# PCB_Telemetria_2020.net
KiCad netlist of a schematic drawn in EAGLE
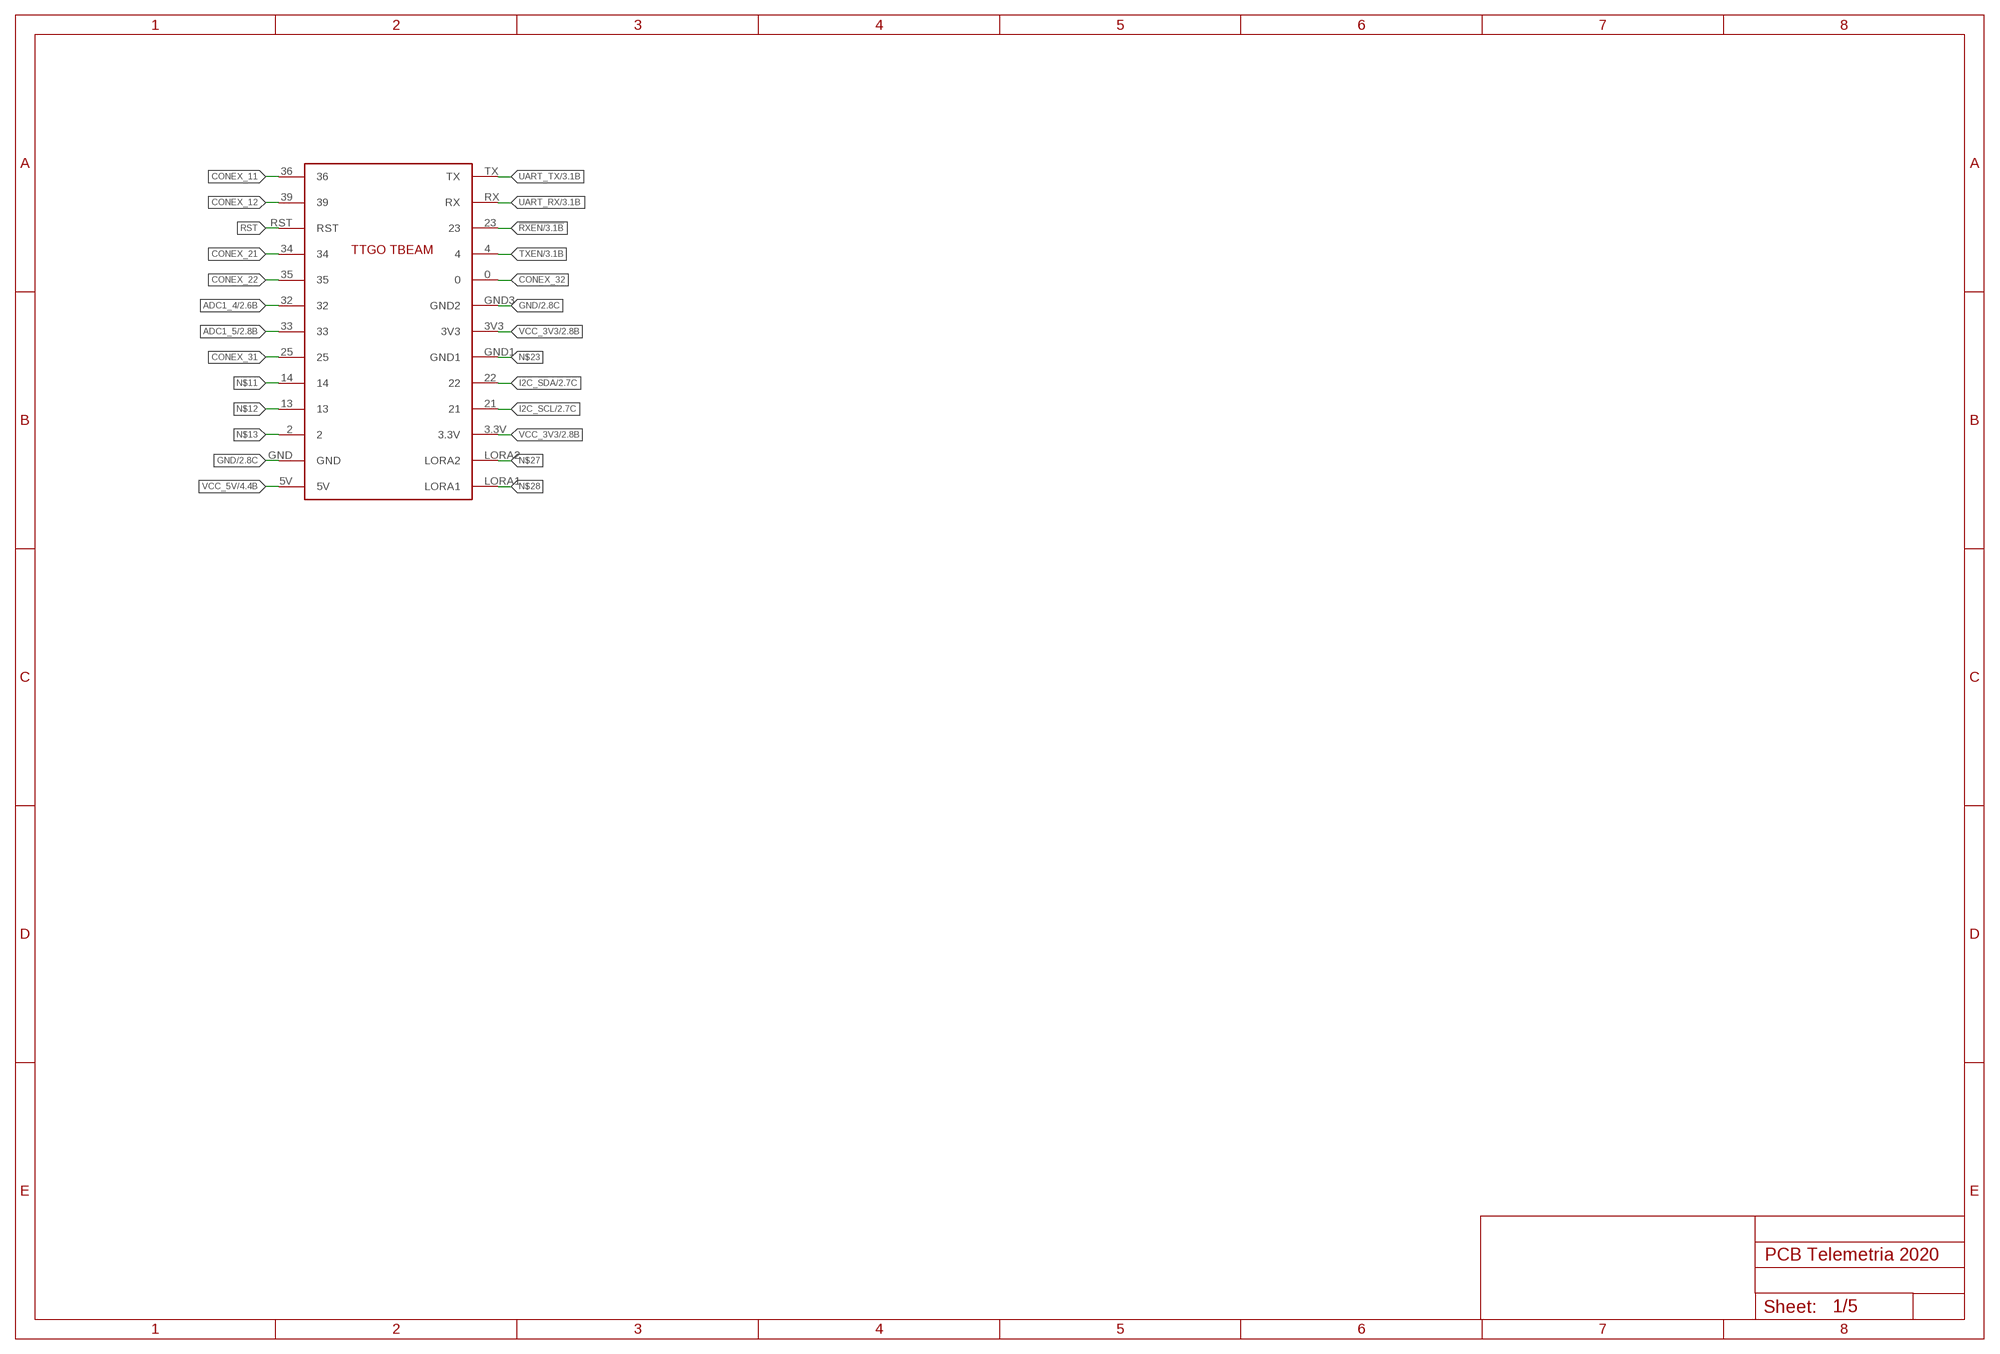
[diagram p0: schematic, sheet 1]
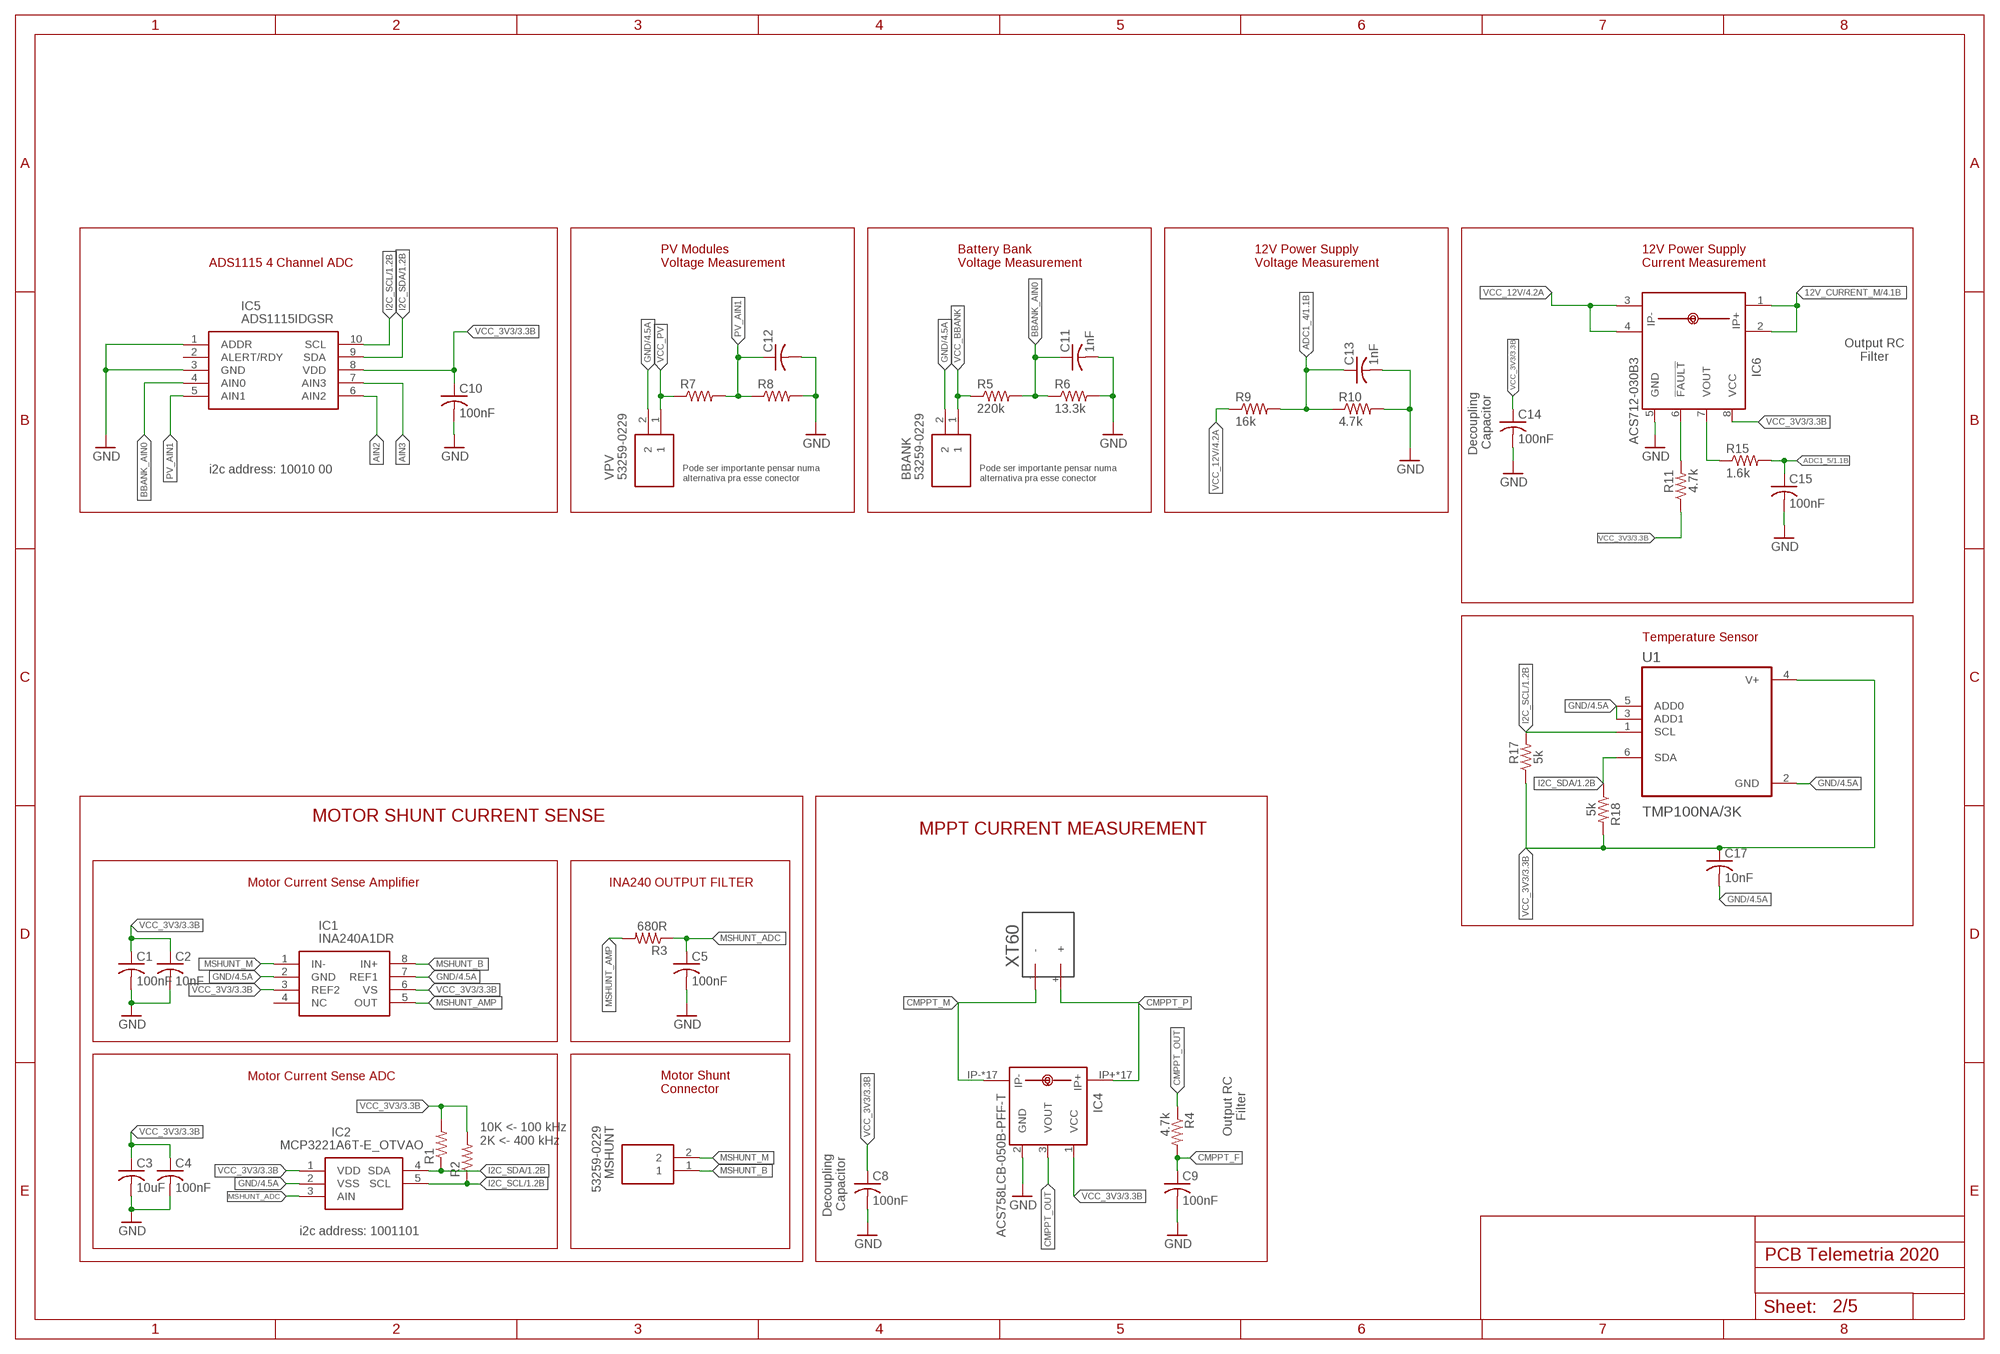
[diagram p1: schematic, sheet 2]
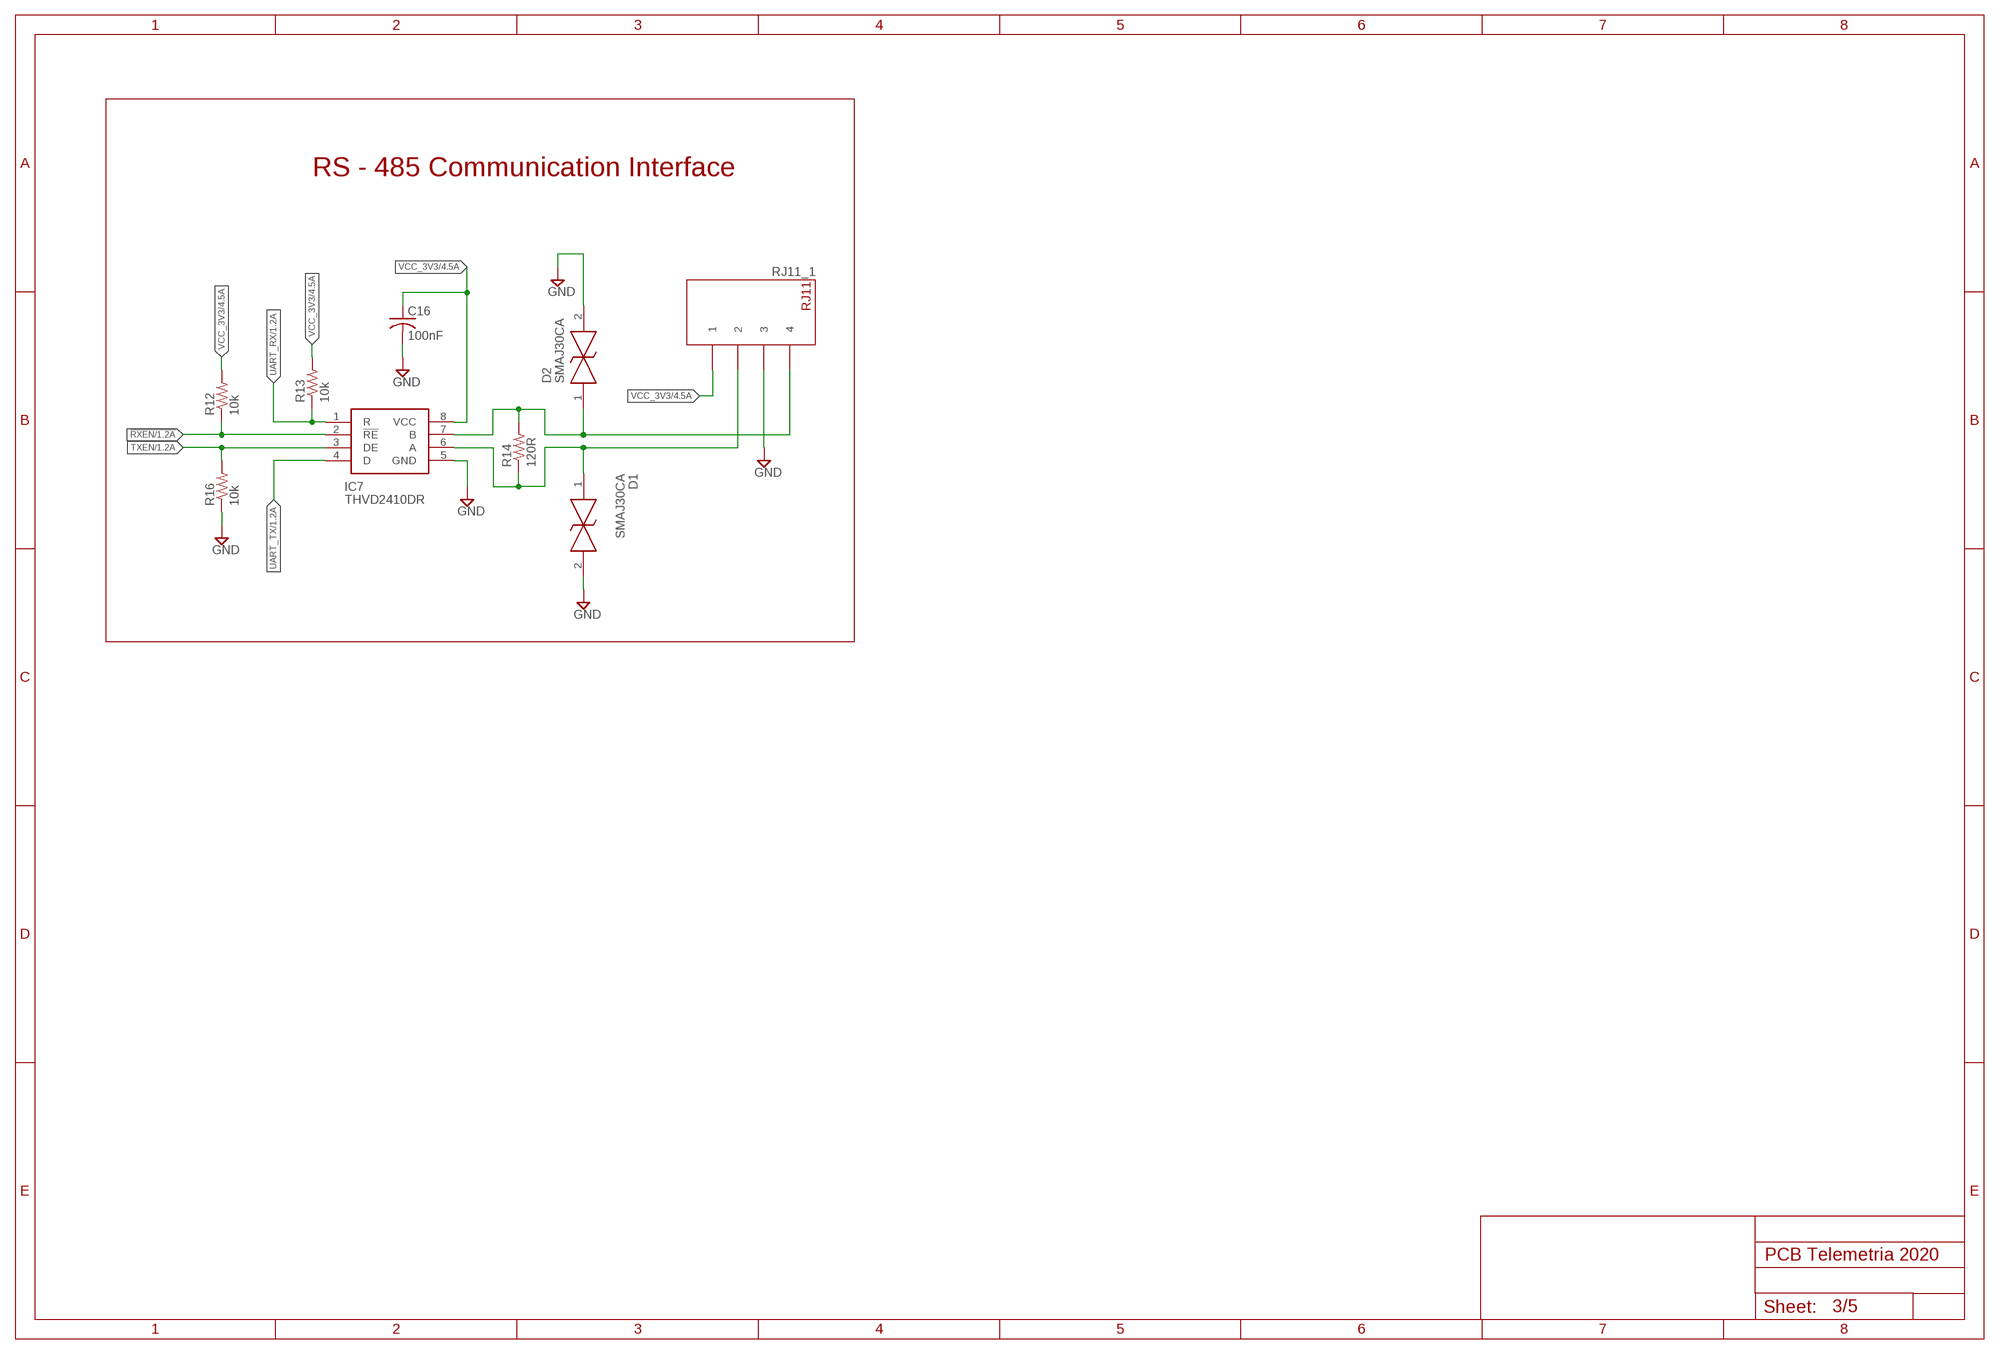
[diagram p2: schematic, sheet 3]
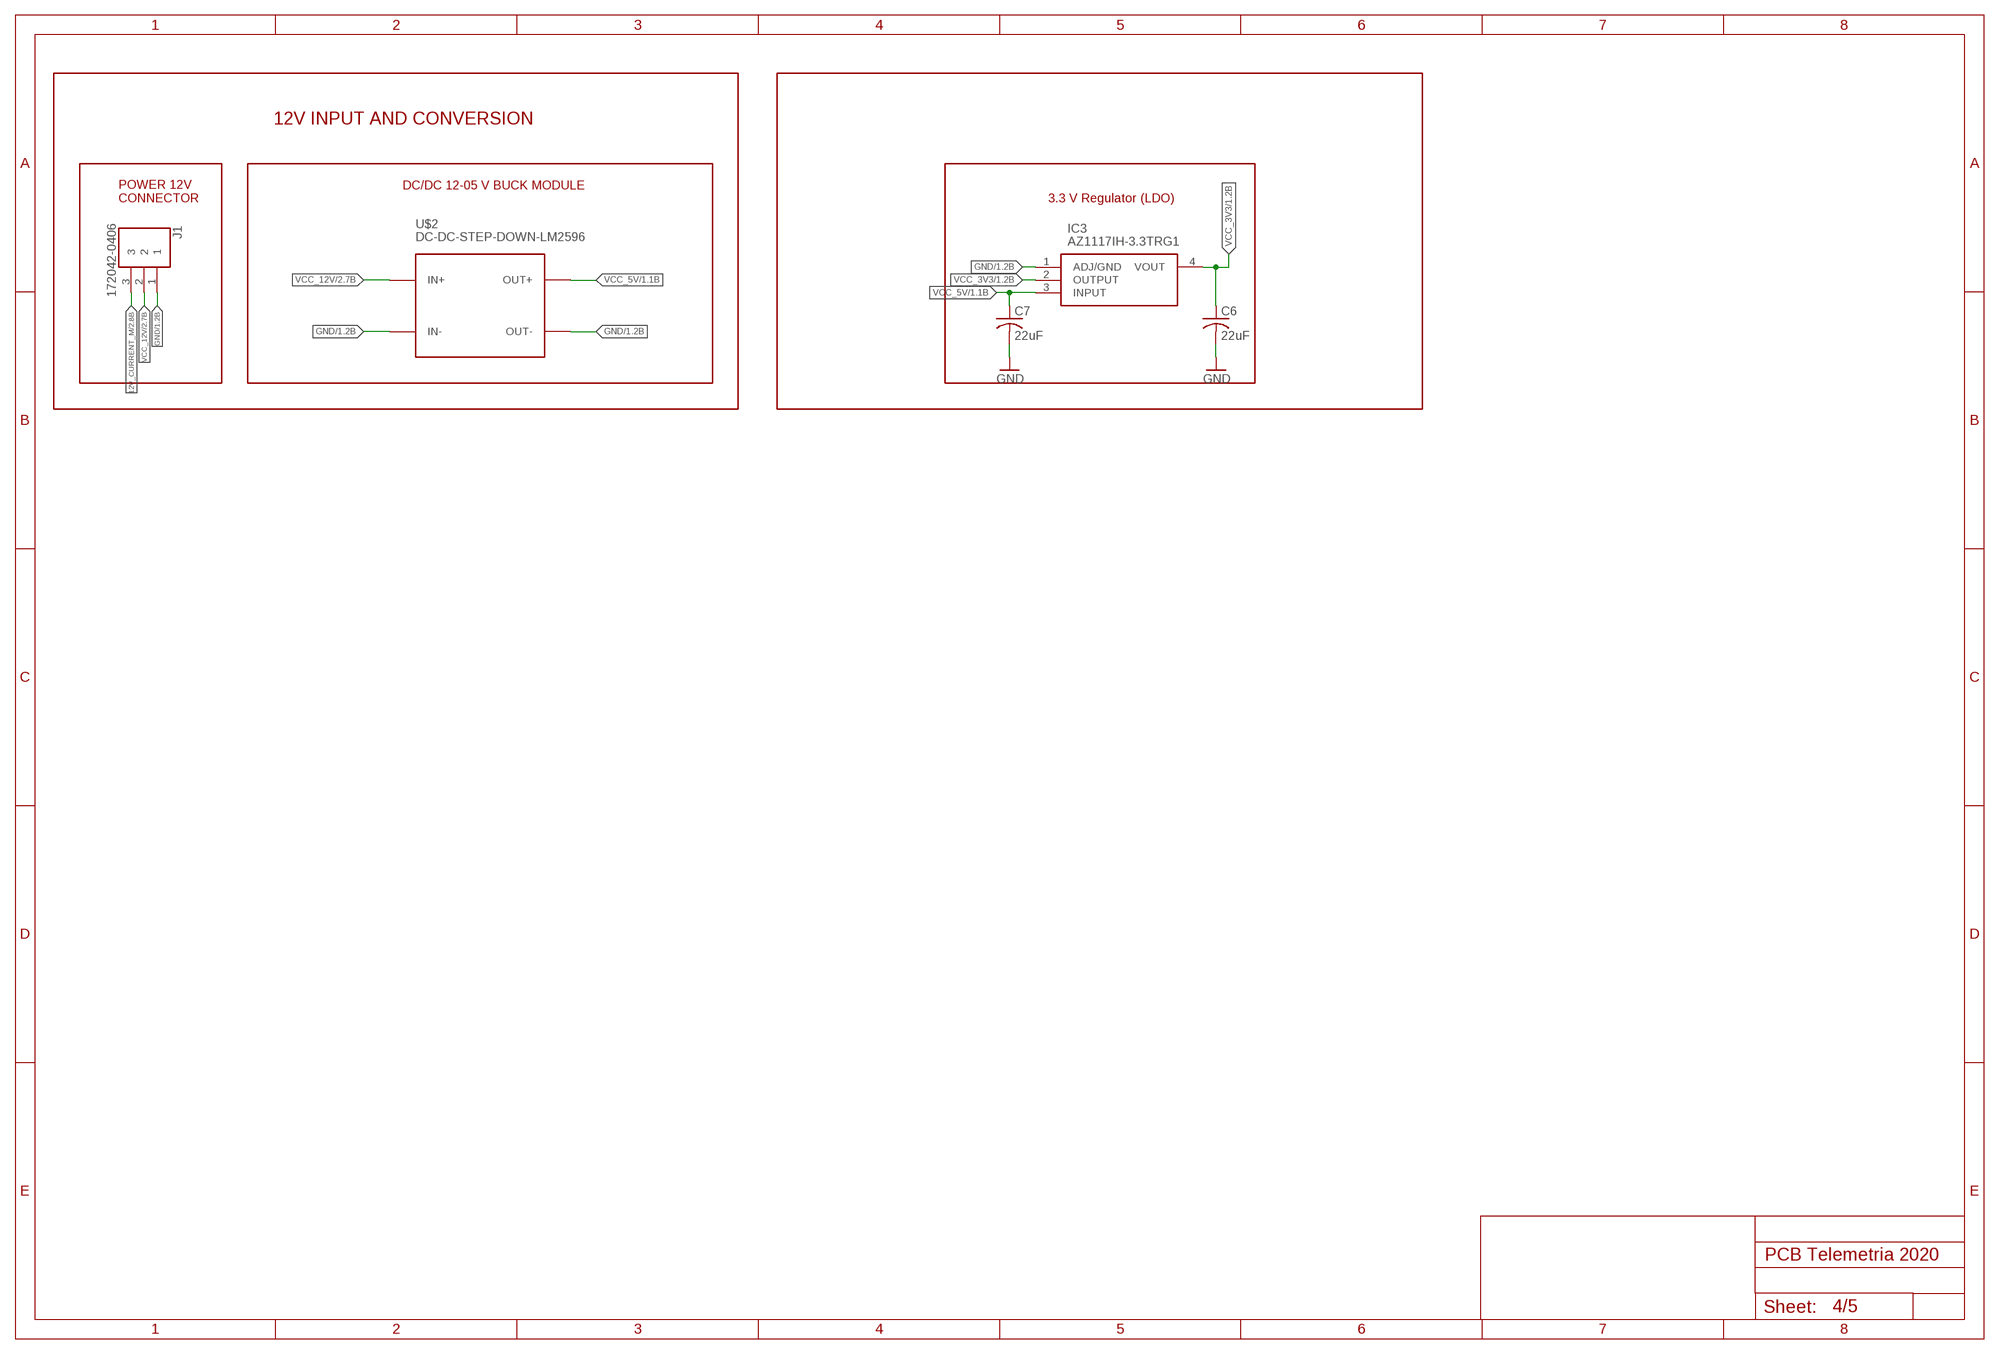
[diagram p3: schematic, sheet 4]
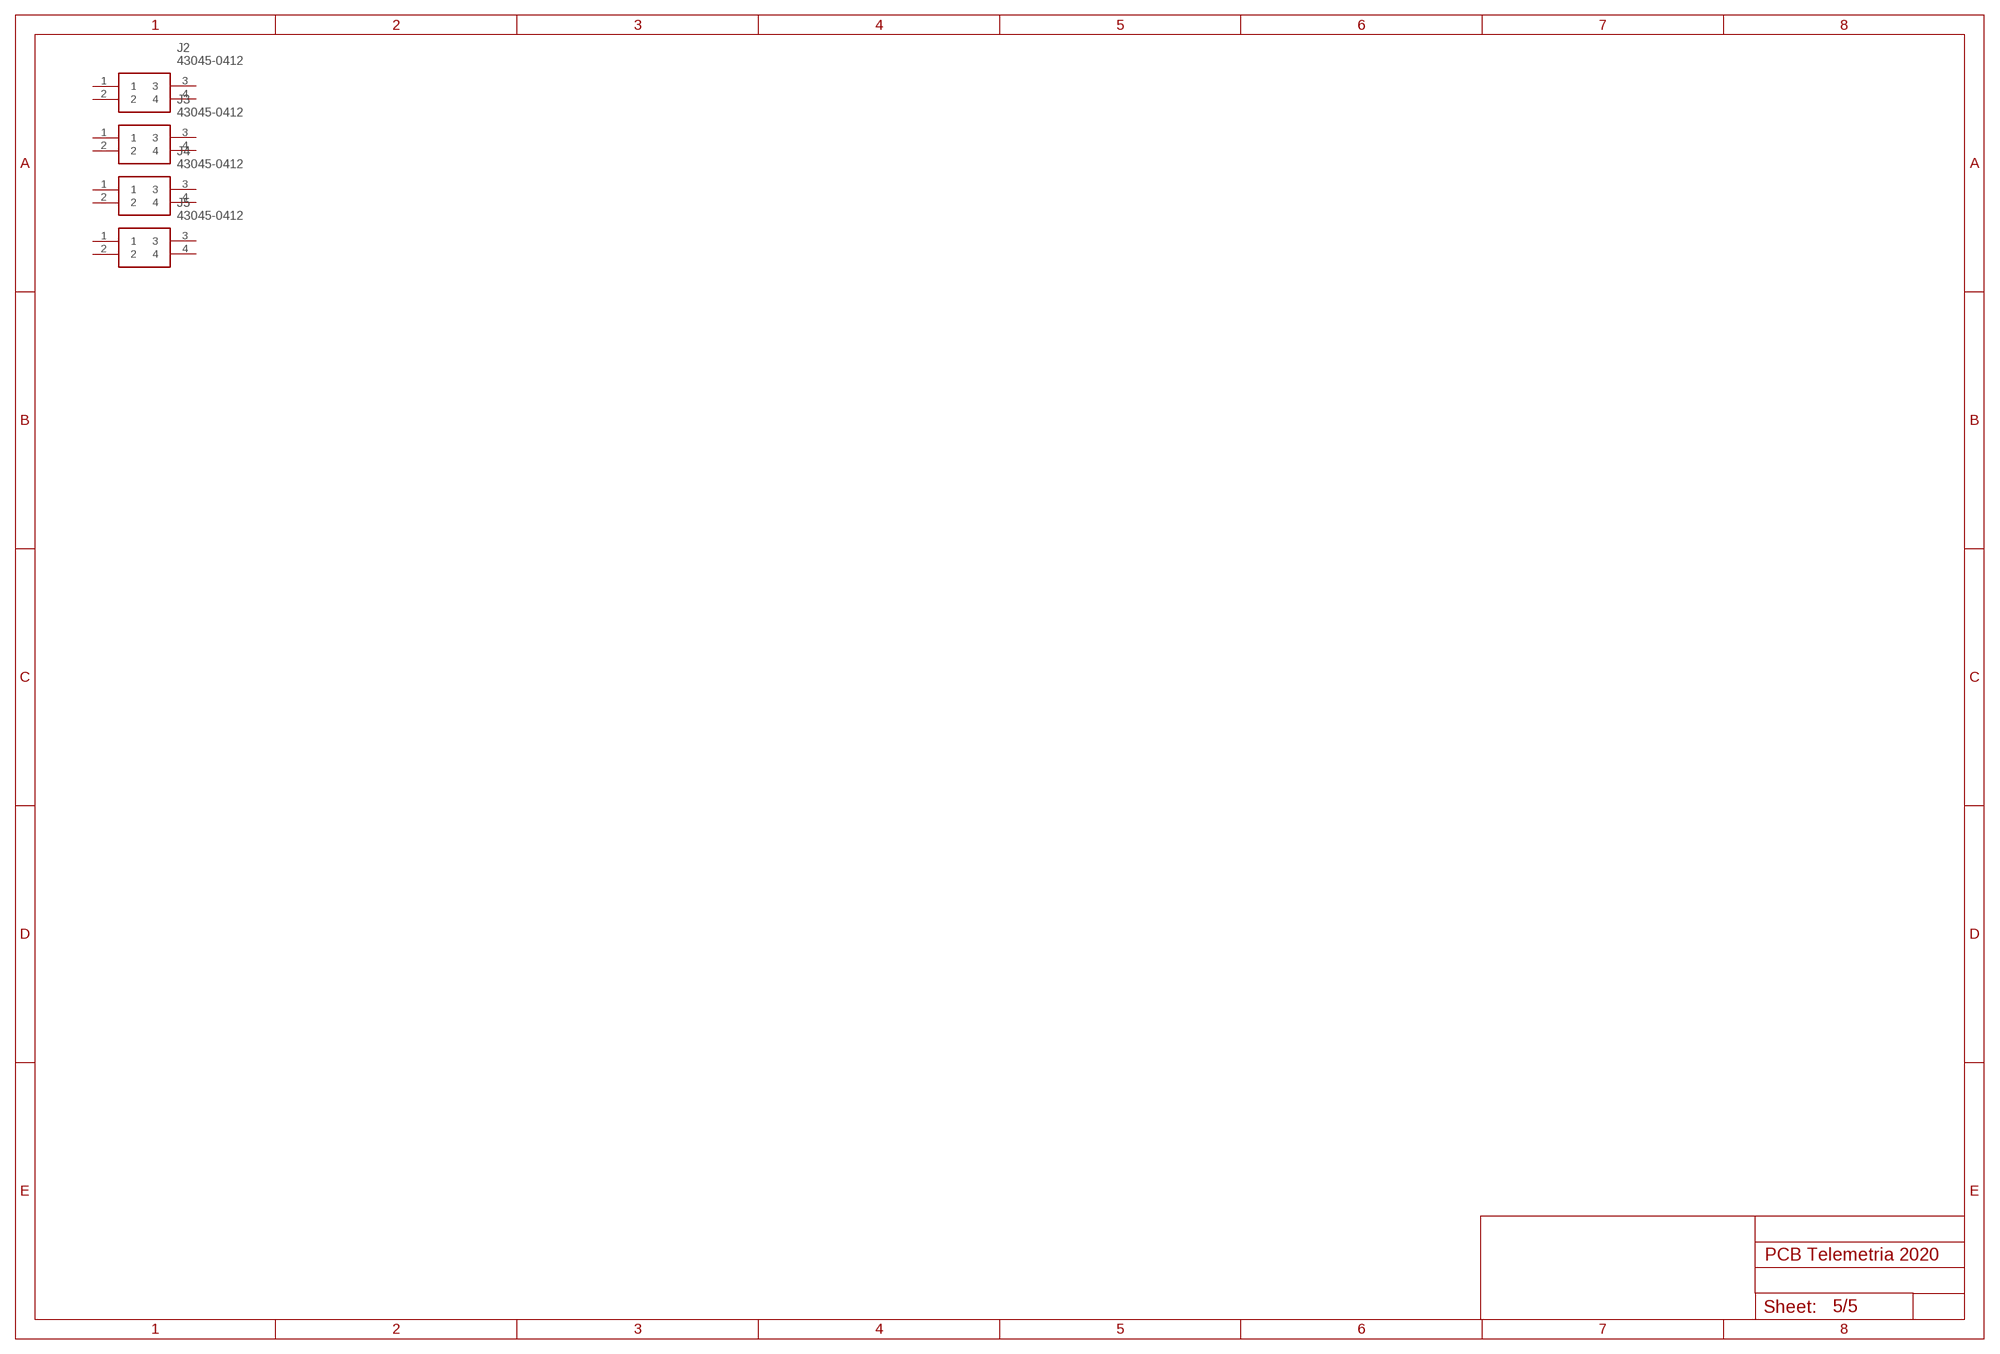
[diagram p4: schematic, sheet 5]

(export (version "E")
  (design (tool "Eeschema 10.0.6"))
  (components
    (comp (ref "J2")
      (value "43045-0412")
      (footprint "eagle-import:43045-0412")
      (fields (field (name "MOUSER_PART_NUMBER") "538-43045-0412"))
      (libsource (lib "eagle-import") (part "43045-0412"))
    )
    (comp (ref "J3")
      (value "43045-0412")
      (footprint "eagle-import:43045-0412")
      (fields (field (name "MOUSER_PART_NUMBER") "538-43045-0412"))
      (libsource (lib "eagle-import") (part "43045-0412"))
    )
    (comp (ref "J4")
      (value "43045-0412")
      (footprint "eagle-import:43045-0412")
      (fields (field (name "MOUSER_PART_NUMBER") "538-43045-0412"))
      (libsource (lib "eagle-import") (part "43045-0412"))
    )
    (comp (ref "J5")
      (value "43045-0412")
      (footprint "eagle-import:43045-0412")
      (fields (field (name "MOUSER_PART_NUMBER") "538-43045-0412"))
      (libsource (lib "eagle-import") (part "43045-0412"))
    )
    (comp (ref "C16")
      (value "100nF")
      (footprint "eagle-import:C0805")
      (libsource (lib "eagle-import") (part "C-USC0805"))
    )
    (comp (ref "D1")
      (value "SMAJ30CA")
      (footprint "eagle-import:DIONM5026X229N")
      (fields (field (name "MOUSER_PART_NUMBER") "576-SMAJ30CA"))
      (libsource (lib "eagle-import") (part "SMAJ30CA"))
    )
    (comp (ref "D2")
      (value "SMAJ30CA")
      (footprint "eagle-import:DIONM5026X229N")
      (fields (field (name "MOUSER_PART_NUMBER") "576-SMAJ30CA"))
      (libsource (lib "eagle-import") (part "SMAJ30CA"))
    )
    (comp (ref "IC7")
      (value "THVD2410DR")
      (footprint "eagle-import:SOIC127P600X175-8N")
      (fields (field (name "MOUSER_PART_NUMBER") "595-THVD2410DR"))
      (libsource (lib "eagle-import") (part "THVD2410DR"))
    )
    (comp (ref "R12")
      (value "10k")
      (footprint "eagle-import:M0805")
      (libsource (lib "eagle-import") (part "R-US_M0805"))
    )
    (comp (ref "R13")
      (value "10k")
      (footprint "eagle-import:M0805")
      (libsource (lib "eagle-import") (part "R-US_M0805"))
    )
    (comp (ref "R14")
      (value "120R")
      (footprint "eagle-import:M0805")
      (libsource (lib "eagle-import") (part "R-US_M0805"))
    )
    (comp (ref "R16")
      (value "10k")
      (footprint "eagle-import:M0805")
      (libsource (lib "eagle-import") (part "R-US_M0805"))
    )
    (comp (ref "RJ11_1")
      (value "TFC44")
      (footprint "eagle-import:TFC44")
      (libsource (lib "eagle-import") (part "TFC44"))
    )
    (comp (ref "C6")
      (value "22uF")
      (footprint "eagle-import:C0805")
      (libsource (lib "eagle-import") (part "C-USC0805"))
    )
    (comp (ref "C7")
      (value "22uF")
      (footprint "eagle-import:C0805")
      (libsource (lib "eagle-import") (part "C-USC0805"))
    )
    (comp (ref "IC3")
      (value "AZ1117IH-3.3TRG1")
      (footprint "eagle-import:SOT230P700X170-4N")
      (fields (field (name "MOUSER_PART_NUMBER") "621-AZ1117IH-3.3TRG1"))
      (libsource (lib "eagle-import") (part "AZ1117IH-3.3TRG1"))
    )
    (comp (ref "J1")
      (value "172042-0406")
      (footprint "eagle-import:MOLEX_172042-0406")
      (fields (field (name "MF") "Molex") (field (name "MP") "172042-0302"))
      (libsource (lib "eagle-import") (part "172042-0406"))
    )
    (comp (ref "U$2")
      (value "DC-DC-STEP-DOWN-LM2596")
      (footprint "eagle-import:DC-DC-STEP-DOWN-LM2596")
      (libsource (lib "eagle-import") (part "DC-DC-STEP-DOWN-LM2596"))
    )
    (comp (ref "U$1")
      (value "TTGOBEAM")
      (footprint "eagle-import:TTGOBEAM")
      (libsource (lib "eagle-import") (part "TTGOBEAM"))
    )
    (comp (ref "BBANK")
      (value "53259-0229")
      (footprint "eagle-import:0532590229")
      (fields (field (name "MOUSER_PART_NUMBER") "538-53259-0229"))
      (libsource (lib "eagle-import") (part "53259-0229"))
    )
    (comp (ref "C1")
      (value "100nF")
      (footprint "eagle-import:C0805")
      (libsource (lib "eagle-import") (part "C-USC0805"))
    )
    (comp (ref "C2")
      (value "10nF")
      (footprint "eagle-import:C0805")
      (libsource (lib "eagle-import") (part "C-USC0805"))
    )
    (comp (ref "C3")
      (value "10uF")
      (footprint "eagle-import:C0805")
      (libsource (lib "eagle-import") (part "C-USC0805"))
    )
    (comp (ref "C4")
      (value "100nF")
      (footprint "eagle-import:C0805")
      (libsource (lib "eagle-import") (part "C-USC0805"))
    )
    (comp (ref "C5")
      (value "100nF")
      (footprint "eagle-import:C0805")
      (libsource (lib "eagle-import") (part "C-USC0805"))
    )
    (comp (ref "C8")
      (value "100nF")
      (footprint "eagle-import:C0805")
      (libsource (lib "eagle-import") (part "C-USC0805"))
    )
    (comp (ref "C9")
      (value "100nF")
      (footprint "eagle-import:C0805")
      (libsource (lib "eagle-import") (part "C-USC0805"))
    )
    (comp (ref "C10")
      (value "100nF")
      (footprint "eagle-import:C0805")
      (libsource (lib "eagle-import") (part "C-USC0805"))
    )
    (comp (ref "C11")
      (value "1nF")
      (footprint "eagle-import:C0805")
      (libsource (lib "eagle-import") (part "C-USC0805"))
    )
    (comp (ref "C12")
      (value "C-USC0805")
      (footprint "eagle-import:C0805")
      (libsource (lib "eagle-import") (part "C-USC0805"))
    )
    (comp (ref "C13")
      (value "1nF")
      (footprint "eagle-import:C0805")
      (libsource (lib "eagle-import") (part "C-USC0805"))
    )
    (comp (ref "C14")
      (value "100nF")
      (footprint "eagle-import:C0805")
      (libsource (lib "eagle-import") (part "C-USC0805"))
    )
    (comp (ref "C15")
      (value "100nF")
      (footprint "eagle-import:C0805")
      (libsource (lib "eagle-import") (part "C-USC0805"))
    )
    (comp (ref "C17")
      (value "10nF")
      (footprint "eagle-import:C0805")
      (libsource (lib "eagle-import") (part "C-USC0805"))
    )
    (comp (ref "IC1")
      (value "INA240A1DR")
      (footprint "eagle-import:SOIC127P600X175-8N")
      (fields (field (name "MOUSER_PART_NUMBER") "595-INA240A1DR"))
      (libsource (lib "eagle-import") (part "INA240A1DR"))
    )
    (comp (ref "IC2")
      (value "MCP3221A6T-E_OTVAO")
      (footprint "eagle-import:SOT95P280X145-5N")
      (fields
        (field (name "MANUFACTURER_PART_NUMBER") "MCP3221A6T-E/OTVAO")
        (field (name "MOUSER_PART_NUMBER") "579-MCP3221A6TEOTVAO")
      )
      (libsource (lib "eagle-import") (part "MCP3221A6T-E_OTVAO"))
    )
    (comp (ref "IC4")
      (value "ACS758LCB-050B-PFF-T")
      (footprint "eagle-import:CB-PFF")
      (libsource (lib "eagle-import") (part "ACS758LCB-050B-PFF-T"))
    )
    (comp (ref "IC5")
      (value "ADS1115IDGSR")
      (footprint "eagle-import:SOP50P490X110-10N")
      (fields (field (name "MOUSER_PART_NUMBER") "595-ADS1115IDGSR"))
      (libsource (lib "eagle-import") (part "ADS1115IDGSR"))
    )
    (comp (ref "IC6")
      (value "ACS712-030B3")
      (footprint "eagle-import:SOIC8")
      (libsource (lib "eagle-import") (part "ACS712-LC"))
    )
    (comp (ref "MSHUNT")
      (value "53259-0229")
      (footprint "eagle-import:0532590229")
      (fields (field (name "MOUSER_PART_NUMBER") "538-53259-0229"))
      (libsource (lib "eagle-import") (part "53259-0229"))
    )
    (comp (ref "R1")
      (value "R-US_R0805")
      (footprint "eagle-import:R0805")
      (libsource (lib "eagle-import") (part "R-US_R0805"))
    )
    (comp (ref "R2")
      (value "R-US_R0805")
      (footprint "eagle-import:R0805")
      (libsource (lib "eagle-import") (part "R-US_R0805"))
    )
    (comp (ref "R3")
      (value "680R")
      (footprint "eagle-import:R0805")
      (libsource (lib "eagle-import") (part "R-US_R0805"))
    )
    (comp (ref "R4")
      (value "4.7k")
      (footprint "eagle-import:R0805")
      (libsource (lib "eagle-import") (part "R-US_R0805"))
    )
    (comp (ref "R5")
      (value "220k")
      (footprint "eagle-import:R0805")
      (libsource (lib "eagle-import") (part "R-US_R0805"))
    )
    (comp (ref "R6")
      (value "13.3k")
      (footprint "eagle-import:R0805")
      (libsource (lib "eagle-import") (part "R-US_R0805"))
    )
    (comp (ref "R7")
      (value "R-US_R0805")
      (footprint "eagle-import:R0805")
      (libsource (lib "eagle-import") (part "R-US_R0805"))
    )
    (comp (ref "R8")
      (value "R-US_R0805")
      (footprint "eagle-import:R0805")
      (libsource (lib "eagle-import") (part "R-US_R0805"))
    )
    (comp (ref "R9")
      (value "16k")
      (footprint "eagle-import:R0805")
      (libsource (lib "eagle-import") (part "R-US_R0805"))
    )
    (comp (ref "R10")
      (value "4.7k")
      (footprint "eagle-import:R0805")
      (libsource (lib "eagle-import") (part "R-US_R0805"))
    )
    (comp (ref "R11")
      (value "4.7k")
      (footprint "eagle-import:R0805")
      (libsource (lib "eagle-import") (part "R-US_R0805"))
    )
    (comp (ref "R15")
      (value "1.6k")
      (footprint "eagle-import:R0805")
      (libsource (lib "eagle-import") (part "R-US_R0805"))
    )
    (comp (ref "R17")
      (value "5k")
      (footprint "eagle-import:R0805")
      (libsource (lib "eagle-import") (part "R-US_R0805"))
    )
    (comp (ref "R18")
      (value "5k")
      (footprint "eagle-import:R0805")
      (libsource (lib "eagle-import") (part "R-US_R0805"))
    )
    (comp (ref "U$3")
      (value "XT60")
      (footprint "eagle-import:XT60")
      (libsource (lib "eagle-import") (part "XT60"))
    )
    (comp (ref "U1")
      (value "TMP100NA/3K")
      (footprint "eagle-import:SOT95P280X145-6N")
      (fields (field (name "MF") "Texas Instruments"))
      (libsource (lib "eagle-import") (part "TMP100NA/3K"))
    )
    (comp (ref "VPV")
      (value "53259-0229")
      (footprint "eagle-import:0532590229")
      (fields (field (name "MOUSER_PART_NUMBER") "538-53259-0229"))
      (libsource (lib "eagle-import") (part "53259-0229"))
    )
  )
  (nets
    (net (code "1") (name "12V_CURRENT_M") (class "Default")
      (node (ref "IC6") (pin "1") (pinfunction "IP+_1") (pintype "passive"))
      (node (ref "IC6") (pin "2") (pinfunction "IP+1_2") (pintype "passive"))
      (node (ref "J1") (pin "3") (pinfunction "3_3") (pintype "passive"))
    )
    (net (code "2") (name "ADC1_4") (class "Default")
      (node (ref "C13") (pin "1") (pinfunction "1_1") (pintype "passive"))
      (node (ref "R10") (pin "1") (pinfunction "1_1") (pintype "passive"))
      (node (ref "R9") (pin "2") (pinfunction "2_2") (pintype "passive"))
      (node (ref "U$1") (pin "32") (pinfunction "32_32") (pintype "bidirectional"))
    )
    (net (code "3") (name "ADC1_5") (class "Default")
      (node (ref "C15") (pin "1") (pinfunction "1_1") (pintype "passive"))
      (node (ref "R15") (pin "2") (pinfunction "2_2") (pintype "passive"))
      (node (ref "U$1") (pin "33") (pinfunction "33_33") (pintype "bidirectional"))
    )
    (net (code "4") (name "AIN2") (class "Default")
      (node (ref "IC5") (pin "6") (pinfunction "AIN2_6") (pintype "bidirectional"))
    )
    (net (code "5") (name "AIN3") (class "Default")
      (node (ref "IC5") (pin "7") (pinfunction "AIN3_7") (pintype "bidirectional"))
    )
    (net (code "6") (name "BBANK_AIN0") (class "Default")
      (node (ref "C11") (pin "1") (pinfunction "1_1") (pintype "passive"))
      (node (ref "IC5") (pin "4") (pinfunction "AIN0_4") (pintype "bidirectional"))
      (node (ref "R5") (pin "2") (pinfunction "2_2") (pintype "passive"))
      (node (ref "R6") (pin "1") (pinfunction "1_1") (pintype "passive"))
    )
    (net (code "7") (name "CMPPT_F") (class "Default")
      (node (ref "C9") (pin "1") (pinfunction "1_1") (pintype "passive"))
      (node (ref "R4") (pin "2") (pinfunction "2_2") (pintype "passive"))
    )
    (net (code "8") (name "CMPPT_M") (class "Default")
      (node (ref "IC4") (pin "IP-") (pinfunction "IP-_IP-") (pintype "passive"))
      (node (ref "IC4") (pin "IP-@10") (pinfunction "IP-_IP-@10") (pintype "passive"))
      (node (ref "IC4") (pin "IP-@11") (pinfunction "IP-_IP-@11") (pintype "passive"))
      (node (ref "IC4") (pin "IP-@12") (pinfunction "IP-_IP-@12") (pintype "passive"))
      (node (ref "IC4") (pin "IP-@13") (pinfunction "IP-_IP-@13") (pintype "passive"))
      (node (ref "IC4") (pin "IP-@14") (pinfunction "IP-_IP-@14") (pintype "passive"))
      (node (ref "IC4") (pin "IP-@15") (pinfunction "IP-_IP-@15") (pintype "passive"))
      (node (ref "IC4") (pin "IP-@16") (pinfunction "IP-_IP-@16") (pintype "passive"))
      (node (ref "IC4") (pin "IP-@17") (pinfunction "IP-_IP-@17") (pintype "passive"))
      (node (ref "IC4") (pin "IP-@2") (pinfunction "IP-_IP-@2") (pintype "passive"))
      (node (ref "IC4") (pin "IP-@3") (pinfunction "IP-_IP-@3") (pintype "passive"))
      (node (ref "IC4") (pin "IP-@4") (pinfunction "IP-_IP-@4") (pintype "passive"))
      (node (ref "IC4") (pin "IP-@5") (pinfunction "IP-_IP-@5") (pintype "passive"))
      (node (ref "IC4") (pin "IP-@6") (pinfunction "IP-_IP-@6") (pintype "passive"))
      (node (ref "IC4") (pin "IP-@7") (pinfunction "IP-_IP-@7") (pintype "passive"))
      (node (ref "IC4") (pin "IP-@8") (pinfunction "IP-_IP-@8") (pintype "passive"))
      (node (ref "IC4") (pin "IP-@9") (pinfunction "IP-_IP-@9") (pintype "passive"))
      (node (ref "U$3") (pin "-") (pinfunction "-_-") (pintype "bidirectional"))
    )
    (net (code "9") (name "CMPPT_OUT") (class "Default")
      (node (ref "IC4") (pin "3") (pinfunction "VOUT_3") (pintype "output"))
      (node (ref "R4") (pin "1") (pinfunction "1_1") (pintype "passive"))
    )
    (net (code "10") (name "CMPPT_P") (class "Default")
      (node (ref "IC4") (pin "IP+") (pinfunction "IP+_IP+") (pintype "passive"))
      (node (ref "IC4") (pin "IP+@10") (pinfunction "IP+_IP+@10") (pintype "passive"))
      (node (ref "IC4") (pin "IP+@11") (pinfunction "IP+_IP+@11") (pintype "passive"))
      (node (ref "IC4") (pin "IP+@12") (pinfunction "IP+_IP+@12") (pintype "passive"))
      (node (ref "IC4") (pin "IP+@13") (pinfunction "IP+_IP+@13") (pintype "passive"))
      (node (ref "IC4") (pin "IP+@14") (pinfunction "IP+_IP+@14") (pintype "passive"))
      (node (ref "IC4") (pin "IP+@15") (pinfunction "IP+_IP+@15") (pintype "passive"))
      (node (ref "IC4") (pin "IP+@16") (pinfunction "IP+_IP+@16") (pintype "passive"))
      (node (ref "IC4") (pin "IP+@17") (pinfunction "IP+_IP+@17") (pintype "passive"))
      (node (ref "IC4") (pin "IP+@2") (pinfunction "IP+_IP+@2") (pintype "passive"))
      (node (ref "IC4") (pin "IP+@3") (pinfunction "IP+_IP+@3") (pintype "passive"))
      (node (ref "IC4") (pin "IP+@4") (pinfunction "IP+_IP+@4") (pintype "passive"))
      (node (ref "IC4") (pin "IP+@5") (pinfunction "IP+_IP+@5") (pintype "passive"))
      (node (ref "IC4") (pin "IP+@6") (pinfunction "IP+_IP+@6") (pintype "passive"))
      (node (ref "IC4") (pin "IP+@7") (pinfunction "IP+_IP+@7") (pintype "passive"))
      (node (ref "IC4") (pin "IP+@8") (pinfunction "IP+_IP+@8") (pintype "passive"))
      (node (ref "IC4") (pin "IP+@9") (pinfunction "IP+_IP+@9") (pintype "passive"))
      (node (ref "U$3") (pin "+") (pinfunction "+_+") (pintype "bidirectional"))
    )
    (net (code "11") (name "CONEX_11") (class "Default")
      (node (ref "U$1") (pin "36") (pinfunction "36_36") (pintype "bidirectional"))
    )
    (net (code "12") (name "CONEX_12") (class "Default")
      (node (ref "U$1") (pin "39") (pinfunction "39_39") (pintype "bidirectional"))
    )
    (net (code "13") (name "CONEX_21") (class "Default")
      (node (ref "U$1") (pin "34") (pinfunction "34_34") (pintype "bidirectional"))
    )
    (net (code "14") (name "CONEX_22") (class "Default")
      (node (ref "U$1") (pin "35") (pinfunction "35_35") (pintype "bidirectional"))
    )
    (net (code "15") (name "CONEX_31") (class "Default")
      (node (ref "U$1") (pin "25") (pinfunction "25_25") (pintype "bidirectional"))
    )
    (net (code "16") (name "CONEX_32") (class "Default")
      (node (ref "U$1") (pin "0") (pinfunction "0_0") (pintype "bidirectional"))
    )
    (net (code "17") (name "GND") (class "Default")
      (node (ref "BBANK") (pin "2") (pinfunction "2_2") (pintype "bidirectional"))
      (node (ref "C1") (pin "2") (pinfunction "2_2") (pintype "passive"))
      (node (ref "C10") (pin "2") (pinfunction "2_2") (pintype "passive"))
      (node (ref "C11") (pin "2") (pinfunction "2_2") (pintype "passive"))
      (node (ref "C12") (pin "2") (pinfunction "2_2") (pintype "passive"))
      (node (ref "C13") (pin "2") (pinfunction "2_2") (pintype "passive"))
      (node (ref "C14") (pin "2") (pinfunction "2_2") (pintype "passive"))
      (node (ref "C15") (pin "2") (pinfunction "2_2") (pintype "passive"))
      (node (ref "C16") (pin "2") (pinfunction "2_2") (pintype "passive"))
      (node (ref "C17") (pin "2") (pinfunction "2_2") (pintype "passive"))
      (node (ref "C2") (pin "2") (pinfunction "2_2") (pintype "passive"))
      (node (ref "C3") (pin "2") (pinfunction "2_2") (pintype "passive"))
      (node (ref "C4") (pin "2") (pinfunction "2_2") (pintype "passive"))
      (node (ref "C5") (pin "2") (pinfunction "2_2") (pintype "passive"))
      (node (ref "C6") (pin "2") (pinfunction "2_2") (pintype "passive"))
      (node (ref "C7") (pin "2") (pinfunction "2_2") (pintype "passive"))
      (node (ref "C8") (pin "2") (pinfunction "2_2") (pintype "passive"))
      (node (ref "C9") (pin "2") (pinfunction "2_2") (pintype "passive"))
      (node (ref "D1") (pin "2") (pinfunction "2_2") (pintype "bidirectional"))
      (node (ref "D2") (pin "2") (pinfunction "2_2") (pintype "bidirectional"))
      (node (ref "IC1") (pin "2") (pinfunction "GND_2") (pintype "bidirectional"))
      (node (ref "IC1") (pin "7") (pinfunction "REF1_7") (pintype "bidirectional"))
      (node (ref "IC2") (pin "2") (pinfunction "VSS_2") (pintype "bidirectional"))
      (node (ref "IC3") (pin "1") (pinfunction "ADJ/GND_1") (pintype "bidirectional"))
      (node (ref "IC4") (pin "2") (pinfunction "GND_2") (pintype "power_in"))
      (node (ref "IC5") (pin "1") (pinfunction "ADDR_1") (pintype "bidirectional"))
      (node (ref "IC5") (pin "3") (pinfunction "GND_3") (pintype "bidirectional"))
      (node (ref "IC6") (pin "5") (pinfunction "GND_5") (pintype "power_in"))
      (node (ref "IC7") (pin "5") (pinfunction "GND_5") (pintype "bidirectional"))
      (node (ref "J1") (pin "1") (pinfunction "1_1") (pintype "passive"))
      (node (ref "R10") (pin "2") (pinfunction "2_2") (pintype "passive"))
      (node (ref "R16") (pin "1") (pinfunction "1_1") (pintype "passive"))
      (node (ref "R6") (pin "2") (pinfunction "2_2") (pintype "passive"))
      (node (ref "R8") (pin "2") (pinfunction "2_2") (pintype "passive"))
      (node (ref "RJ11_1") (pin "P$3") (pinfunction "3_P$3") (pintype "bidirectional"))
      (node (ref "U$1") (pin "GND") (pinfunction "GND_GND") (pintype "bidirectional"))
      (node (ref "U$1") (pin "GND3") (pinfunction "GND2_GND3") (pintype "bidirectional"))
      (node (ref "U$2") (pin "IN-") (pinfunction "IN-_IN-") (pintype "bidirectional"))
      (node (ref "U$2") (pin "OUT-") (pinfunction "OUT-_OUT-") (pintype "bidirectional"))
      (node (ref "U1") (pin "2") (pinfunction "GND_2") (pintype "power_in"))
      (node (ref "U1") (pin "3") (pinfunction "ADD1_3") (pintype "input"))
      (node (ref "U1") (pin "5") (pinfunction "ADD0_5") (pintype "input"))
      (node (ref "VPV") (pin "2") (pinfunction "2_2") (pintype "bidirectional"))
    )
    (net (code "18") (name "I2C_SCL") (class "Default")
      (node (ref "IC2") (pin "5") (pinfunction "SCL_5") (pintype "bidirectional"))
      (node (ref "IC5") (pin "10") (pinfunction "SCL_10") (pintype "bidirectional"))
      (node (ref "R17") (pin "2") (pinfunction "2_2") (pintype "passive"))
      (node (ref "R2") (pin "1") (pinfunction "1_1") (pintype "passive"))
      (node (ref "U$1") (pin "21") (pinfunction "21_21") (pintype "bidirectional"))
      (node (ref "U1") (pin "1") (pinfunction "SCL_1") (pintype "input"))
    )
    (net (code "19") (name "I2C_SDA") (class "Default")
      (node (ref "IC2") (pin "4") (pinfunction "SDA_4") (pintype "bidirectional"))
      (node (ref "IC5") (pin "9") (pinfunction "SDA_9") (pintype "bidirectional"))
      (node (ref "R1") (pin "1") (pinfunction "1_1") (pintype "passive"))
      (node (ref "R18") (pin "1") (pinfunction "1_1") (pintype "passive"))
      (node (ref "U$1") (pin "22") (pinfunction "22_22") (pintype "bidirectional"))
      (node (ref "U1") (pin "6") (pinfunction "SDA_6") (pintype "bidirectional"))
    )
    (net (code "20") (name "MSHUNT_ADC") (class "Default")
      (node (ref "C5") (pin "1") (pinfunction "1_1") (pintype "passive"))
      (node (ref "IC2") (pin "3") (pinfunction "AIN_3") (pintype "bidirectional"))
      (node (ref "R3") (pin "1") (pinfunction "1_1") (pintype "passive"))
    )
    (net (code "21") (name "MSHUNT_AMP") (class "Default")
      (node (ref "IC1") (pin "5") (pinfunction "OUT_5") (pintype "bidirectional"))
      (node (ref "R3") (pin "2") (pinfunction "2_2") (pintype "passive"))
    )
    (net (code "22") (name "MSHUNT_B") (class "Default")
      (node (ref "IC1") (pin "8") (pinfunction "IN+_8") (pintype "bidirectional"))
      (node (ref "MSHUNT") (pin "1") (pinfunction "1_1") (pintype "bidirectional"))
    )
    (net (code "23") (name "MSHUNT_M") (class "Default")
      (node (ref "IC1") (pin "1") (pinfunction "IN-_1") (pintype "bidirectional"))
      (node (ref "MSHUNT") (pin "2") (pinfunction "2_2") (pintype "bidirectional"))
    )
    (net (code "24") (name "N$11") (class "Default")
      (node (ref "U$1") (pin "14") (pinfunction "14_14") (pintype "bidirectional"))
    )
    (net (code "25") (name "N$12") (class "Default")
      (node (ref "U$1") (pin "13") (pinfunction "13_13") (pintype "bidirectional"))
    )
    (net (code "26") (name "N$13") (class "Default")
      (node (ref "U$1") (pin "2") (pinfunction "2_2") (pintype "bidirectional"))
    )
    (net (code "27") (name "N$23") (class "Default")
      (node (ref "U$1") (pin "GND1") (pinfunction "GND1_GND1") (pintype "bidirectional"))
    )
    (net (code "28") (name "N$27") (class "Default")
      (node (ref "U$1") (pin "LORA2") (pinfunction "LORA2_LORA2") (pintype "bidirectional"))
    )
    (net (code "29") (name "N$28") (class "Default")
      (node (ref "U$1") (pin "LORA1") (pinfunction "LORA1_LORA1") (pintype "bidirectional"))
    )
    (net (code "30") (name "Net-(IC6-VOUT)") (class "Default")
      (node (ref "IC6") (pin "7") (pinfunction "VOUT_7") (pintype "output"))
      (node (ref "R15") (pin "1") (pinfunction "1_1") (pintype "passive"))
    )
    (net (code "31") (name "Net-(IC6-~{FAULT})") (class "Default")
      (node (ref "IC6") (pin "6") (pinfunction "~{FAULT}_6") (pintype "bidirectional"))
      (node (ref "R11") (pin "2") (pinfunction "2_2") (pintype "passive"))
    )
    (net (code "32") (name "Net-(IC7-A)") (class "Default")
      (node (ref "D1") (pin "1") (pinfunction "1_1") (pintype "bidirectional"))
      (node (ref "IC7") (pin "6") (pinfunction "A_6") (pintype "bidirectional"))
      (node (ref "R14") (pin "1") (pinfunction "1_1") (pintype "passive"))
      (node (ref "RJ11_1") (pin "P$2") (pinfunction "2_P$2") (pintype "bidirectional"))
    )
    (net (code "33") (name "Net-(IC7-B)") (class "Default")
      (node (ref "D2") (pin "1") (pinfunction "1_1") (pintype "bidirectional"))
      (node (ref "IC7") (pin "7") (pinfunction "B_7") (pintype "bidirectional"))
      (node (ref "R14") (pin "2") (pinfunction "2_2") (pintype "passive"))
      (node (ref "RJ11_1") (pin "P$4") (pinfunction "4_P$4") (pintype "bidirectional"))
    )
    (net (code "34") (name "PV_AIN1") (class "Default")
      (node (ref "C12") (pin "1") (pinfunction "1_1") (pintype "passive"))
      (node (ref "IC5") (pin "5") (pinfunction "AIN1_5") (pintype "bidirectional"))
      (node (ref "R7") (pin "2") (pinfunction "2_2") (pintype "passive"))
      (node (ref "R8") (pin "1") (pinfunction "1_1") (pintype "passive"))
    )
    (net (code "35") (name "RST") (class "Default")
      (node (ref "U$1") (pin "RST") (pinfunction "RST_RST") (pintype "bidirectional"))
    )
    (net (code "36") (name "TXEN") (class "Default")
      (node (ref "IC7") (pin "3") (pinfunction "DE_3") (pintype "bidirectional"))
      (node (ref "R16") (pin "2") (pinfunction "2_2") (pintype "passive"))
      (node (ref "U$1") (pin "4") (pinfunction "4_4") (pintype "bidirectional"))
    )
    (net (code "37") (name "UART_RX") (class "Default")
      (node (ref "IC7") (pin "1") (pinfunction "R_1") (pintype "bidirectional"))
      (node (ref "R13") (pin "1") (pinfunction "1_1") (pintype "passive"))
      (node (ref "U$1") (pin "RX") (pinfunction "RX_RX") (pintype "bidirectional"))
    )
    (net (code "38") (name "UART_TX") (class "Default")
      (node (ref "IC7") (pin "4") (pinfunction "D_4") (pintype "bidirectional"))
      (node (ref "U$1") (pin "TX") (pinfunction "TX_TX") (pintype "bidirectional"))
    )
    (net (code "39") (name "VCC_3V3") (class "Default")
      (node (ref "C1") (pin "1") (pinfunction "1_1") (pintype "passive"))
      (node (ref "C10") (pin "1") (pinfunction "1_1") (pintype "passive"))
      (node (ref "C14") (pin "1") (pinfunction "1_1") (pintype "passive"))
      (node (ref "C16") (pin "1") (pinfunction "1_1") (pintype "passive"))
      (node (ref "C17") (pin "1") (pinfunction "1_1") (pintype "passive"))
      (node (ref "C2") (pin "1") (pinfunction "1_1") (pintype "passive"))
      (node (ref "C3") (pin "1") (pinfunction "1_1") (pintype "passive"))
      (node (ref "C4") (pin "1") (pinfunction "1_1") (pintype "passive"))
      (node (ref "C6") (pin "1") (pinfunction "1_1") (pintype "passive"))
      (node (ref "C8") (pin "1") (pinfunction "1_1") (pintype "passive"))
      (node (ref "IC1") (pin "3") (pinfunction "REF2_3") (pintype "bidirectional"))
      (node (ref "IC1") (pin "6") (pinfunction "VS_6") (pintype "bidirectional"))
      (node (ref "IC2") (pin "1") (pinfunction "VDD_1") (pintype "bidirectional"))
      (node (ref "IC3") (pin "2") (pinfunction "OUTPUT_2") (pintype "bidirectional"))
      (node (ref "IC3") (pin "4") (pinfunction "VOUT_4") (pintype "bidirectional"))
      (node (ref "IC4") (pin "1") (pinfunction "VCC_1") (pintype "power_in"))
      (node (ref "IC5") (pin "8") (pinfunction "VDD_8") (pintype "bidirectional"))
      (node (ref "IC6") (pin "8") (pinfunction "VCC_8") (pintype "power_in"))
      (node (ref "IC7") (pin "8") (pinfunction "VCC_8") (pintype "bidirectional"))
      (node (ref "R1") (pin "2") (pinfunction "2_2") (pintype "passive"))
      (node (ref "R11") (pin "1") (pinfunction "1_1") (pintype "passive"))
      (node (ref "R12") (pin "2") (pinfunction "2_2") (pintype "passive"))
      (node (ref "R13") (pin "2") (pinfunction "2_2") (pintype "passive"))
      (node (ref "R17") (pin "1") (pinfunction "1_1") (pintype "passive"))
      (node (ref "R18") (pin "2") (pinfunction "2_2") (pintype "passive"))
      (node (ref "R2") (pin "2") (pinfunction "2_2") (pintype "passive"))
      (node (ref "RJ11_1") (pin "P$1") (pinfunction "1_P$1") (pintype "bidirectional"))
      (node (ref "U$1") (pin "3.3V") (pinfunction "3.3V_3.3V") (pintype "bidirectional"))
      (node (ref "U$1") (pin "3V3") (pinfunction "3V3_3V3") (pintype "bidirectional"))
      (node (ref "U1") (pin "4") (pinfunction "V+_4") (pintype "power_in"))
    )
    (net (code "40") (name "VCC_5V") (class "Default")
      (node (ref "C7") (pin "1") (pinfunction "1_1") (pintype "passive"))
      (node (ref "IC3") (pin "3") (pinfunction "INPUT_3") (pintype "bidirectional"))
      (node (ref "U$1") (pin "5V") (pinfunction "5V_5V") (pintype "bidirectional"))
      (node (ref "U$2") (pin "OUT+") (pinfunction "OUT+_OUT+") (pintype "bidirectional"))
    )
    (net (code "41") (name "VCC_12V") (class "Default")
      (node (ref "IC6") (pin "3") (pinfunction "IP-_3") (pintype "passive"))
      (node (ref "IC6") (pin "4") (pinfunction "IP-1_4") (pintype "passive"))
      (node (ref "J1") (pin "2") (pinfunction "2_2") (pintype "passive"))
      (node (ref "R9") (pin "1") (pinfunction "1_1") (pintype "passive"))
      (node (ref "U$2") (pin "IN+") (pinfunction "IN+_IN+") (pintype "bidirectional"))
    )
    (net (code "42") (name "VCC_BBANK") (class "Default")
      (node (ref "BBANK") (pin "1") (pinfunction "1_1") (pintype "bidirectional"))
      (node (ref "R5") (pin "1") (pinfunction "1_1") (pintype "passive"))
    )
    (net (code "43") (name "VCC_PV") (class "Default")
      (node (ref "R7") (pin "1") (pinfunction "1_1") (pintype "passive"))
      (node (ref "VPV") (pin "1") (pinfunction "1_1") (pintype "bidirectional"))
    )
    (net (code "44") (name "unconnected-(IC1-NC-Pad4)") (class "Default")
      (node (ref "IC1") (pin "4") (pinfunction "NC_4") (pintype "no_connect"))
    )
    (net (code "45") (name "unconnected-(IC5-ALERT{slash}RDY-Pad2)") (class "Default")
      (node (ref "IC5") (pin "2") (pinfunction "ALERT/RDY_2") (pintype "bidirectional"))
    )
    (net (code "46") (name "unconnected-(J2-Pad1)") (class "Default")
      (node (ref "J2") (pin "1") (pinfunction "1_1") (pintype "bidirectional"))
    )
    (net (code "47") (name "unconnected-(J2-Pad2)") (class "Default")
      (node (ref "J2") (pin "2") (pinfunction "2_2") (pintype "bidirectional"))
    )
    (net (code "48") (name "unconnected-(J2-Pad3)") (class "Default")
      (node (ref "J2") (pin "3") (pinfunction "3_3") (pintype "bidirectional"))
    )
    (net (code "49") (name "unconnected-(J2-Pad4)") (class "Default")
      (node (ref "J2") (pin "4") (pinfunction "4_4") (pintype "bidirectional"))
    )
    (net (code "50") (name "unconnected-(J3-Pad1)") (class "Default")
      (node (ref "J3") (pin "1") (pinfunction "1_1") (pintype "bidirectional"))
    )
    (net (code "51") (name "unconnected-(J3-Pad2)") (class "Default")
      (node (ref "J3") (pin "2") (pinfunction "2_2") (pintype "bidirectional"))
    )
    (net (code "52") (name "unconnected-(J3-Pad3)") (class "Default")
      (node (ref "J3") (pin "3") (pinfunction "3_3") (pintype "bidirectional"))
    )
    (net (code "53") (name "unconnected-(J3-Pad4)") (class "Default")
      (node (ref "J3") (pin "4") (pinfunction "4_4") (pintype "bidirectional"))
    )
    (net (code "54") (name "unconnected-(J4-Pad1)") (class "Default")
      (node (ref "J4") (pin "1") (pinfunction "1_1") (pintype "bidirectional"))
    )
    (net (code "55") (name "unconnected-(J4-Pad2)") (class "Default")
      (node (ref "J4") (pin "2") (pinfunction "2_2") (pintype "bidirectional"))
    )
    (net (code "56") (name "unconnected-(J4-Pad3)") (class "Default")
      (node (ref "J4") (pin "3") (pinfunction "3_3") (pintype "bidirectional"))
    )
    (net (code "57") (name "unconnected-(J4-Pad4)") (class "Default")
      (node (ref "J4") (pin "4") (pinfunction "4_4") (pintype "bidirectional"))
    )
    (net (code "58") (name "unconnected-(J5-Pad1)") (class "Default")
      (node (ref "J5") (pin "1") (pinfunction "1_1") (pintype "bidirectional"))
    )
    (net (code "59") (name "unconnected-(J5-Pad2)") (class "Default")
      (node (ref "J5") (pin "2") (pinfunction "2_2") (pintype "bidirectional"))
    )
    (net (code "60") (name "unconnected-(J5-Pad3)") (class "Default")
      (node (ref "J5") (pin "3") (pinfunction "3_3") (pintype "bidirectional"))
    )
    (net (code "61") (name "unconnected-(J5-Pad4)") (class "Default")
      (node (ref "J5") (pin "4") (pinfunction "4_4") (pintype "bidirectional"))
    )
    (net (code "62") (name "~{RXEN}") (class "Default")
      (node (ref "IC7") (pin "2") (pinfunction "~{RE}_2") (pintype "bidirectional"))
      (node (ref "R12") (pin "1") (pinfunction "1_1") (pintype "passive"))
      (node (ref "U$1") (pin "23") (pinfunction "23_23") (pintype "bidirectional"))
    )
  )
)
